# vetinari_clock_reference.net
KiCad netlist of a schematic drawn in EAGLE
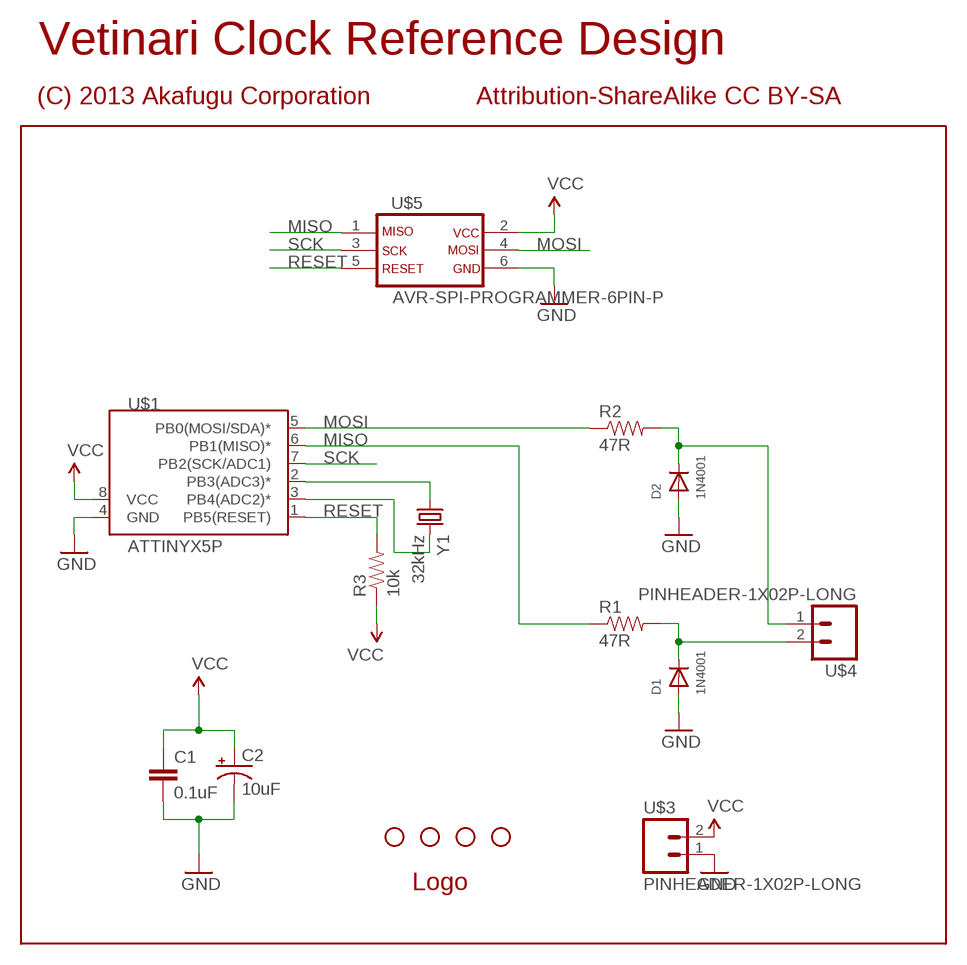
[diagram p0: schematic, sheet 1]

(export (version "E")
  (design (tool "Eeschema 10.0.6"))
  (components
    (comp (ref "C1")
      (value "0.1uF")
      (footprint "eagle-import:CAP-PTH-2.54MM")
      (libsource (lib "eagle-import") (part "CAP-PTH-2.54MM"))
    )
    (comp (ref "C2")
      (value "10uF")
      (footprint "eagle-import:CPOL-RADIAL-SLIM")
      (libsource (lib "eagle-import") (part "CAP_POL-RADIAL-SLIM"))
    )
    (comp (ref "D1")
      (value "1N4001")
      (footprint "eagle-import:DIODE-1N4001-BIGHOLES")
      (libsource (lib "eagle-import") (part "DIODE-1N4001-BIGHOLES"))
    )
    (comp (ref "D2")
      (value "1N4001")
      (footprint "eagle-import:DIODE-1N4001-BIGHOLES")
      (libsource (lib "eagle-import") (part "DIODE-1N4001-BIGHOLES"))
    )
    (comp (ref "JP1")
      (value "STAND-OFF")
      (footprint "eagle-import:STAND-OFF")
      (libsource (lib "eagle-import") (part "STAND-OFF"))
    )
    (comp (ref "JP2")
      (value "STAND-OFF")
      (footprint "eagle-import:STAND-OFF")
      (libsource (lib "eagle-import") (part "STAND-OFF"))
    )
    (comp (ref "JP3")
      (value "STAND-OFF")
      (footprint "eagle-import:STAND-OFF")
      (libsource (lib "eagle-import") (part "STAND-OFF"))
    )
    (comp (ref "JP4")
      (value "STAND-OFF")
      (footprint "eagle-import:STAND-OFF")
      (libsource (lib "eagle-import") (part "STAND-OFF"))
    )
    (comp (ref "R1")
      (value "47R")
      (footprint "eagle-import:1_6W-RES-OUTLINE")
      (libsource (lib "eagle-import") (part "RESISTOR-PTH-1/6W-OUTLINE"))
    )
    (comp (ref "R2")
      (value "47R")
      (footprint "eagle-import:1_6W-RES-OUTLINE")
      (libsource (lib "eagle-import") (part "RESISTOR-PTH-1/6W-OUTLINE"))
    )
    (comp (ref "R3")
      (value "10k")
      (footprint "eagle-import:1_6W-RES-OUTLINE")
      (libsource (lib "eagle-import") (part "RESISTOR-PTH-1/6W-OUTLINE"))
    )
    (comp (ref "U$1")
      (value "ATTINYX5P")
      (footprint "eagle-import:DIL-8")
      (libsource (lib "eagle-import") (part "ATTINYX5P"))
    )
    (comp (ref "U$3")
      (value "PINHEADER-1X02P-LONG")
      (footprint "eagle-import:1X02-LONG")
      (libsource (lib "eagle-import") (part "PINHEADER-1X02P-LONG"))
    )
    (comp (ref "U$4")
      (value "PINHEADER-1X02P-LONG")
      (footprint "eagle-import:1X02-LONG")
      (libsource (lib "eagle-import") (part "PINHEADER-1X02P-LONG"))
    )
    (comp (ref "U$5")
      (value "AVR-SPI-PROGRAMMER-6PIN-P")
      (footprint "eagle-import:2X03")
      (libsource (lib "eagle-import") (part "AVR-SPI-PROGRAMMER-6PIN-P"))
    )
    (comp (ref "U$6")
      (value "OSHW-LOGO-OUTLINE")
      (footprint "eagle-import:OSHW-LOGO-OUTLINE")
      (libsource (lib "eagle-import") (part "OSHW-LOGO-OUTLINE"))
    )
    (comp (ref "Y1")
      (value "32kHz")
      (footprint "eagle-import:TC38H")
      (libsource (lib "eagle-import") (part "CRYSTAL-TC38H"))
    )
  )
  (nets
    (net (code "1") (name "/MISO") (class "Default")
      (node (ref "R1") (pin "1") (pinfunction "1_1") (pintype "passive"))
      (node (ref "U$1") (pin "6") (pinfunction "PB1(MISO)*_6") (pintype "bidirectional"))
      (node (ref "U$5") (pin "1") (pinfunction "1_1") (pintype "passive"))
    )
    (net (code "2") (name "/MOSI") (class "Default")
      (node (ref "R2") (pin "1") (pinfunction "1_1") (pintype "passive"))
      (node (ref "U$1") (pin "5") (pinfunction "PB0(MOSI/SDA)*_5") (pintype "bidirectional"))
      (node (ref "U$5") (pin "4") (pinfunction "4_4") (pintype "passive"))
    )
    (net (code "3") (name "/RESET") (class "Default")
      (node (ref "R3") (pin "2") (pinfunction "2_2") (pintype "passive"))
      (node (ref "U$1") (pin "1") (pinfunction "PB5(RESET)_1") (pintype "bidirectional"))
      (node (ref "U$5") (pin "5") (pinfunction "5_5") (pintype "passive"))
    )
    (net (code "4") (name "/SCK") (class "Default")
      (node (ref "U$1") (pin "7") (pinfunction "PB2(SCK/ADC1)_7") (pintype "bidirectional"))
      (node (ref "U$5") (pin "3") (pinfunction "3_3") (pintype "passive"))
    )
    (net (code "5") (name "GND") (class "Default")
      (node (ref "C1") (pin "2") (pinfunction "2_2") (pintype "passive"))
      (node (ref "C2") (pin "2") (pinfunction "-_2") (pintype "passive"))
      (node (ref "D1") (pin "A") (pinfunction "A_A") (pintype "passive"))
      (node (ref "D2") (pin "A") (pinfunction "A_A") (pintype "passive"))
      (node (ref "U$1") (pin "4") (pinfunction "GND_4") (pintype "bidirectional"))
      (node (ref "U$3") (pin "1") (pinfunction "1_1") (pintype "passive"))
      (node (ref "U$5") (pin "6") (pinfunction "6_6") (pintype "passive"))
    )
    (net (code "6") (name "Net-(D1-PadC)") (class "Default")
      (node (ref "D1") (pin "C") (pinfunction "C_C") (pintype "passive"))
      (node (ref "R1") (pin "2") (pinfunction "2_2") (pintype "passive"))
      (node (ref "U$4") (pin "2") (pinfunction "2_2") (pintype "passive"))
    )
    (net (code "7") (name "Net-(D2-PadC)") (class "Default")
      (node (ref "D2") (pin "C") (pinfunction "C_C") (pintype "passive"))
      (node (ref "R2") (pin "2") (pinfunction "2_2") (pintype "passive"))
      (node (ref "U$4") (pin "1") (pinfunction "1_1") (pintype "passive"))
    )
    (net (code "8") (name "Net-(U$1-PB3(ADC3)*)") (class "Default")
      (node (ref "U$1") (pin "2") (pinfunction "PB3(ADC3)*_2") (pintype "bidirectional"))
      (node (ref "Y1") (pin "1") (pinfunction "1_1") (pintype "passive"))
    )
    (net (code "9") (name "Net-(U$1-PB4(ADC2)*)") (class "Default")
      (node (ref "U$1") (pin "3") (pinfunction "PB4(ADC2)*_3") (pintype "bidirectional"))
      (node (ref "Y1") (pin "2") (pinfunction "2_2") (pintype "passive"))
    )
    (net (code "10") (name "VCC") (class "Default")
      (node (ref "C1") (pin "1") (pinfunction "1_1") (pintype "passive"))
      (node (ref "C2") (pin "1") (pinfunction "+_1") (pintype "passive"))
      (node (ref "R3") (pin "1") (pinfunction "1_1") (pintype "passive"))
      (node (ref "U$1") (pin "8") (pinfunction "VCC_8") (pintype "bidirectional"))
      (node (ref "U$3") (pin "2") (pinfunction "2_2") (pintype "passive"))
      (node (ref "U$5") (pin "2") (pinfunction "2_2") (pintype "passive"))
    )
  )
)
